# ConectoresSalida.net
KiCad netlist of a schematic drawn in Altium Designer
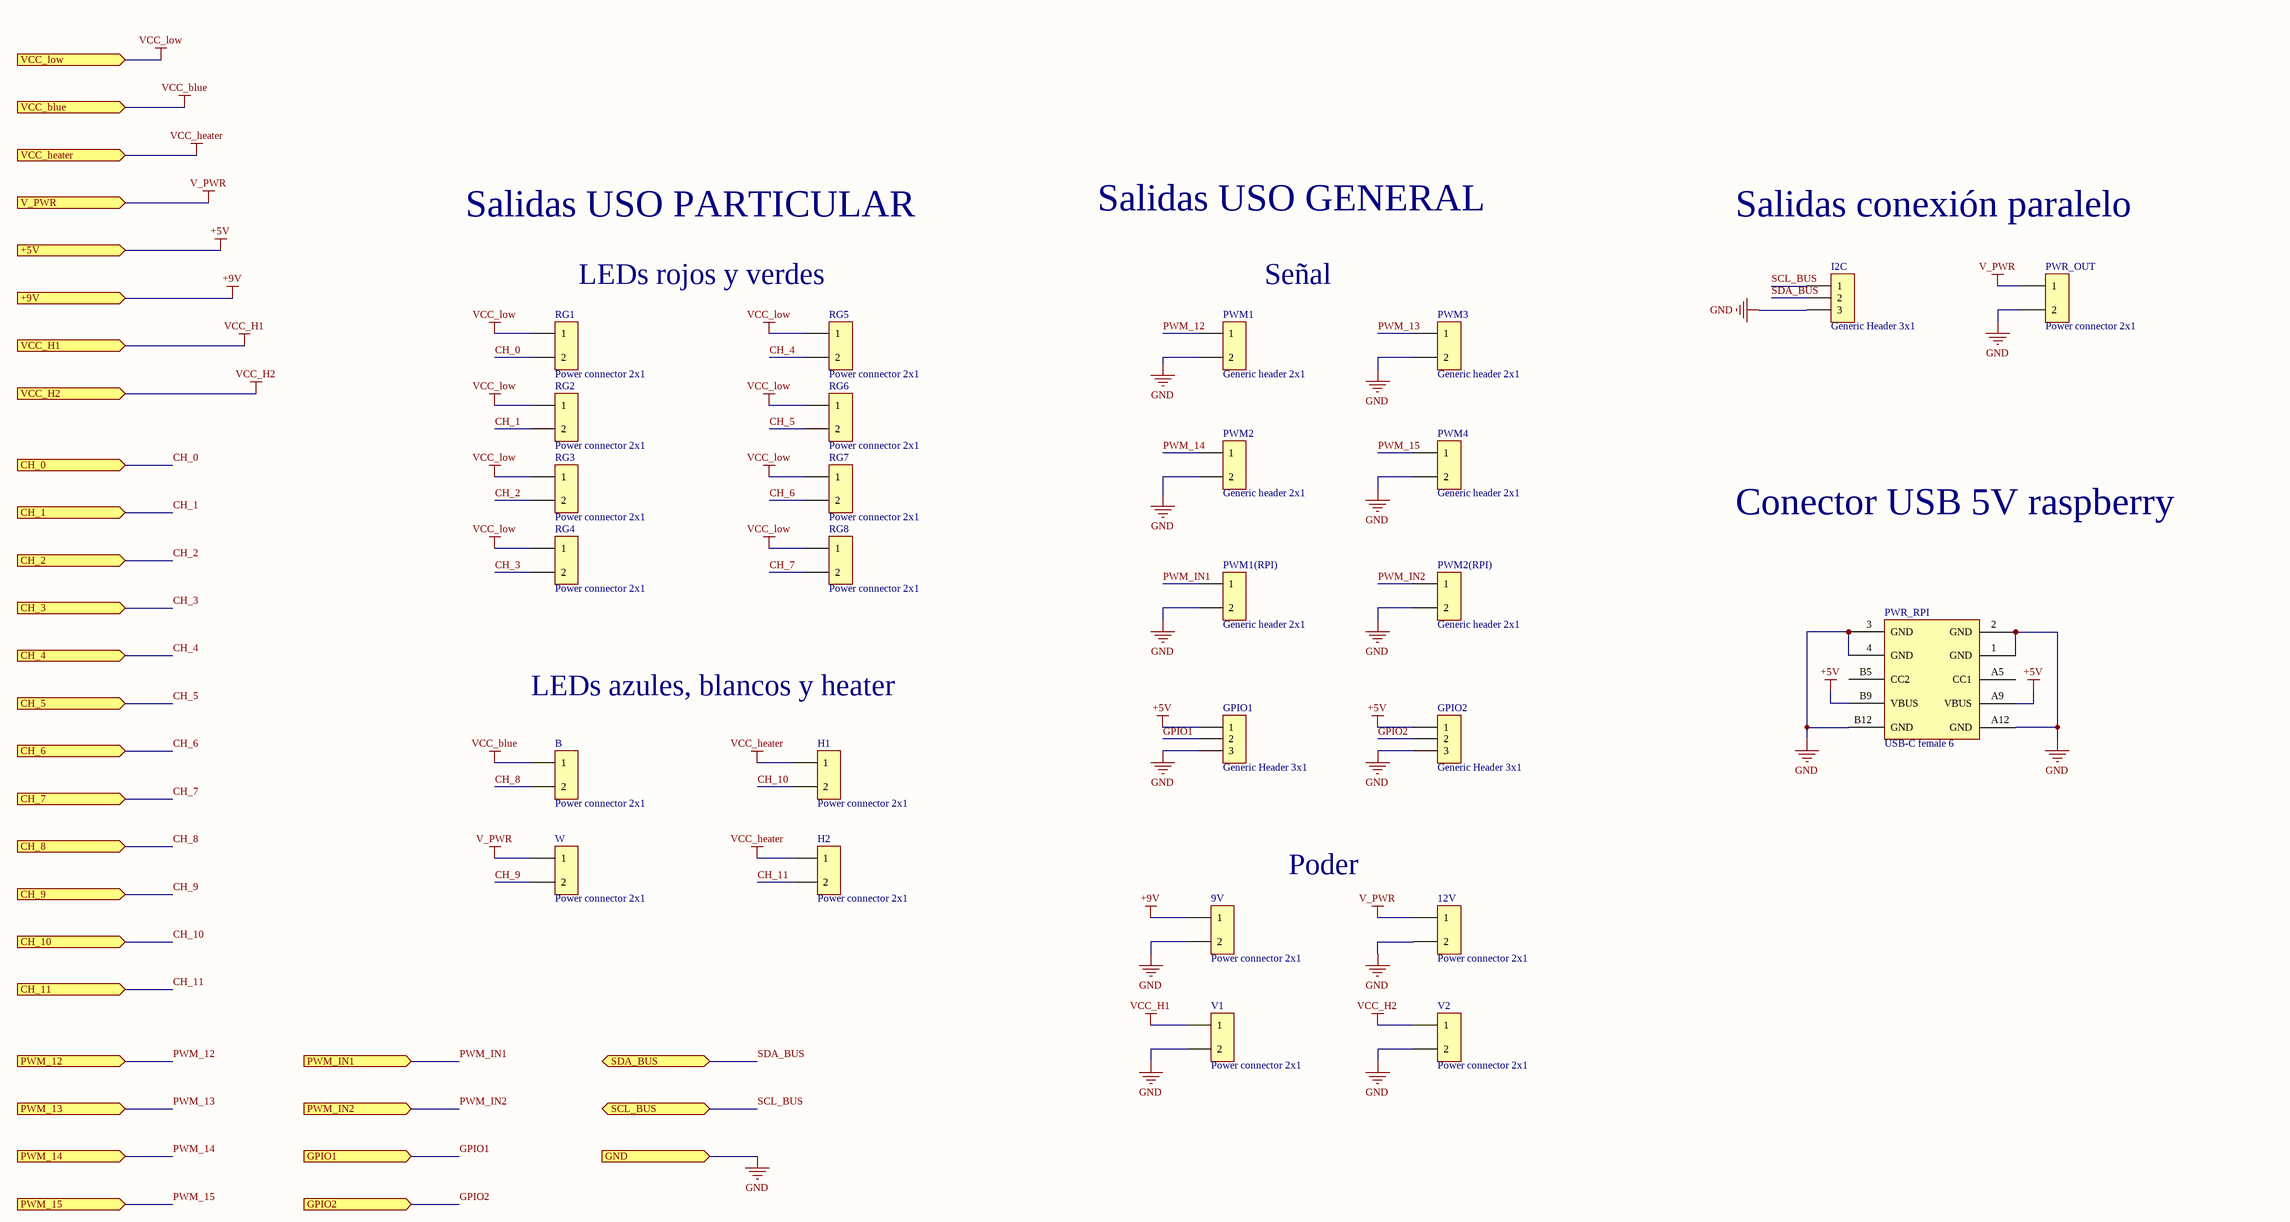
[diagram p0: ConectoresSalida.SchDoc]

(export (version "E")
  (design (tool "Eeschema 10.0.6"))
  (components
    (comp (ref "9V")
      (value "Power connector 2x1")
      (footprint "CONN-TH_430450212")
      (description "Generic Header Power 2pos")
      (fields (field (name "MANUFACTURER") "MOLEX") (field (name "MANUFACTURER PART NUMBER") "430450212"))
      (libsource (lib "IoWLabsConnectors") (part "PC - 2X1"))
    )
    (comp (ref "12V")
      (value "Power connector 2x1")
      (footprint "CONN-TH_430450212")
      (description "Generic Header Power 2pos")
      (fields (field (name "MANUFACTURER") "MOLEX") (field (name "MANUFACTURER PART NUMBER") "430450212"))
      (libsource (lib "IoWLabsConnectors") (part "PC - 2X1"))
    )
    (comp (ref "B")
      (value "Power connector 2x1")
      (footprint "CONN-TH_430450212")
      (description "Generic Header Power 2pos")
      (fields (field (name "MANUFACTURER") "MOLEX") (field (name "MANUFACTURER PART NUMBER") "430450212"))
      (libsource (lib "IoWLabsConnectors") (part "PC - 2X1"))
    )
    (comp (ref "GPIO1")
      (value "Generic Header 3x1")
      (footprint "CONN-TH_A2547WV-3P")
      (description "Generic Header 3pos, 1 row, 2.54 pitch")
      (fields
        (field (name "MANUFACTURER") "CJT(Changjiang Connectors)")
        (field (name "MANUFACTURER PART NUMBER") "A2547WV-3P")
      )
      (libsource (lib "IoWLabsConnectors") (part "Header - 3x1"))
    )
    (comp (ref "GPIO2")
      (value "Generic Header 3x1")
      (footprint "CONN-TH_A2547WV-3P")
      (description "Generic Header 3pos, 1 row, 2.54 pitch")
      (fields
        (field (name "MANUFACTURER") "CJT(Changjiang Connectors)")
        (field (name "MANUFACTURER PART NUMBER") "A2547WV-3P")
      )
      (libsource (lib "IoWLabsConnectors") (part "Header - 3x1"))
    )
    (comp (ref "H1")
      (value "Power connector 2x1")
      (footprint "CONN-TH_430450212")
      (description "Generic Header Power 2pos")
      (fields (field (name "MANUFACTURER") "MOLEX") (field (name "MANUFACTURER PART NUMBER") "430450212"))
      (libsource (lib "IoWLabsConnectors") (part "PC - 2X1"))
    )
    (comp (ref "H2")
      (value "Power connector 2x1")
      (footprint "CONN-TH_430450212")
      (description "Generic Header Power 2pos")
      (fields (field (name "MANUFACTURER") "MOLEX") (field (name "MANUFACTURER PART NUMBER") "430450212"))
      (libsource (lib "IoWLabsConnectors") (part "PC - 2X1"))
    )
    (comp (ref "I2C")
      (value "Generic Header 3x1")
      (footprint "CONN-TH_A2547WV-3P")
      (description "Generic Header 3pos, 1 row, 2.54 pitch")
      (fields
        (field (name "MANUFACTURER") "CJT(Changjiang Connectors)")
        (field (name "MANUFACTURER PART NUMBER") "A2547WV-3P")
      )
      (libsource (lib "IoWLabsConnectors") (part "Header - 3x1"))
    )
    (comp (ref "PWM1")
      (value "Generic header 2x1")
      (footprint "CONN-TH_A2547WV-2P")
      (description "Generic Header 2pos, 1 row, 2.54 pitch")
      (fields
        (field (name "MANUFACTURER") "CJT(Changjiang Connectors)")
        (field (name "MANUFACTURER PART NUMBER") "A2547WV-2P")
      )
      (libsource (lib "IoWLabsConnectors") (part "Header - 2x1"))
    )
    (comp (ref "PWM1(RPI)")
      (value "Generic header 2x1")
      (footprint "CONN-TH_A2547WV-2P")
      (description "Generic Header 2pos, 1 row, 2.54 pitch")
      (fields
        (field (name "MANUFACTURER") "CJT(Changjiang Connectors)")
        (field (name "MANUFACTURER PART NUMBER") "A2547WV-2P")
      )
      (libsource (lib "IoWLabsConnectors") (part "Header - 2x1"))
    )
    (comp (ref "PWM2")
      (value "Generic header 2x1")
      (footprint "CONN-TH_A2547WV-2P")
      (description "Generic Header 2pos, 1 row, 2.54 pitch")
      (fields
        (field (name "MANUFACTURER") "CJT(Changjiang Connectors)")
        (field (name "MANUFACTURER PART NUMBER") "A2547WV-2P")
      )
      (libsource (lib "IoWLabsConnectors") (part "Header - 2x1"))
    )
    (comp (ref "PWM2(RPI)")
      (value "Generic header 2x1")
      (footprint "CONN-TH_A2547WV-2P")
      (description "Generic Header 2pos, 1 row, 2.54 pitch")
      (fields
        (field (name "MANUFACTURER") "CJT(Changjiang Connectors)")
        (field (name "MANUFACTURER PART NUMBER") "A2547WV-2P")
      )
      (libsource (lib "IoWLabsConnectors") (part "Header - 2x1"))
    )
    (comp (ref "PWM3")
      (value "Generic header 2x1")
      (footprint "CONN-TH_A2547WV-2P")
      (description "Generic Header 2pos, 1 row, 2.54 pitch")
      (fields
        (field (name "MANUFACTURER") "CJT(Changjiang Connectors)")
        (field (name "MANUFACTURER PART NUMBER") "A2547WV-2P")
      )
      (libsource (lib "IoWLabsConnectors") (part "Header - 2x1"))
    )
    (comp (ref "PWM4")
      (value "Generic header 2x1")
      (footprint "CONN-TH_A2547WV-2P")
      (description "Generic Header 2pos, 1 row, 2.54 pitch")
      (fields
        (field (name "MANUFACTURER") "CJT(Changjiang Connectors)")
        (field (name "MANUFACTURER PART NUMBER") "A2547WV-2P")
      )
      (libsource (lib "IoWLabsConnectors") (part "Header - 2x1"))
    )
    (comp (ref "PWR_OUT")
      (value "Power connector 2x1")
      (footprint "CONN-TH_430450212")
      (description "Generic Header Power 2pos")
      (fields (field (name "MANUFACTURER") "MOLEX") (field (name "MANUFACTURER PART NUMBER") "430450212"))
      (libsource (lib "IoWLabsConnectors") (part "PC - 2X1"))
    )
    (comp (ref "PWR_RPI")
      (value "USB-C female 6")
      (footprint "USB-C_SMD 6 contacts")
      (description "USB - Type C Female 6 USB Connectors RoHS")
      (fields
        (field (name "MANUFACTURER") "Korean Hroparts Elec")
        (field (name "MANUFACTURER PART NUMBER") "TYPE-C-31-M-17")
      )
      (libsource (lib "IoWLabsConnectors") (part "USB-C female 6"))
    )
    (comp (ref "RG1")
      (value "Power connector 2x1")
      (footprint "CONN-TH_430450212")
      (description "Generic Header Power 2pos")
      (fields (field (name "MANUFACTURER") "MOLEX") (field (name "MANUFACTURER PART NUMBER") "430450212"))
      (libsource (lib "IoWLabsConnectors") (part "PC - 2X1"))
    )
    (comp (ref "RG2")
      (value "Power connector 2x1")
      (footprint "CONN-TH_430450212")
      (description "Generic Header Power 2pos")
      (fields (field (name "MANUFACTURER") "MOLEX") (field (name "MANUFACTURER PART NUMBER") "430450212"))
      (libsource (lib "IoWLabsConnectors") (part "PC - 2X1"))
    )
    (comp (ref "RG3")
      (value "Power connector 2x1")
      (footprint "CONN-TH_430450212")
      (description "Generic Header Power 2pos")
      (fields (field (name "MANUFACTURER") "MOLEX") (field (name "MANUFACTURER PART NUMBER") "430450212"))
      (libsource (lib "IoWLabsConnectors") (part "PC - 2X1"))
    )
    (comp (ref "RG4")
      (value "Power connector 2x1")
      (footprint "CONN-TH_430450212")
      (description "Generic Header Power 2pos")
      (fields (field (name "MANUFACTURER") "MOLEX") (field (name "MANUFACTURER PART NUMBER") "430450212"))
      (libsource (lib "IoWLabsConnectors") (part "PC - 2X1"))
    )
    (comp (ref "RG5")
      (value "Power connector 2x1")
      (footprint "CONN-TH_430450212")
      (description "Generic Header Power 2pos")
      (fields (field (name "MANUFACTURER") "MOLEX") (field (name "MANUFACTURER PART NUMBER") "430450212"))
      (libsource (lib "IoWLabsConnectors") (part "PC - 2X1"))
    )
    (comp (ref "RG6")
      (value "Power connector 2x1")
      (footprint "CONN-TH_430450212")
      (description "Generic Header Power 2pos")
      (fields (field (name "MANUFACTURER") "MOLEX") (field (name "MANUFACTURER PART NUMBER") "430450212"))
      (libsource (lib "IoWLabsConnectors") (part "PC - 2X1"))
    )
    (comp (ref "RG7")
      (value "Power connector 2x1")
      (footprint "CONN-TH_430450212")
      (description "Generic Header Power 2pos")
      (fields (field (name "MANUFACTURER") "MOLEX") (field (name "MANUFACTURER PART NUMBER") "430450212"))
      (libsource (lib "IoWLabsConnectors") (part "PC - 2X1"))
    )
    (comp (ref "RG8")
      (value "Power connector 2x1")
      (footprint "CONN-TH_430450212")
      (description "Generic Header Power 2pos")
      (fields (field (name "MANUFACTURER") "MOLEX") (field (name "MANUFACTURER PART NUMBER") "430450212"))
      (libsource (lib "IoWLabsConnectors") (part "PC - 2X1"))
    )
    (comp (ref "V1")
      (value "Power connector 2x1")
      (footprint "CONN-TH_430450212")
      (description "Generic Header Power 2pos")
      (fields (field (name "MANUFACTURER") "MOLEX") (field (name "MANUFACTURER PART NUMBER") "430450212"))
      (libsource (lib "IoWLabsConnectors") (part "PC - 2X1"))
    )
    (comp (ref "V2")
      (value "Power connector 2x1")
      (footprint "CONN-TH_430450212")
      (description "Generic Header Power 2pos")
      (fields (field (name "MANUFACTURER") "MOLEX") (field (name "MANUFACTURER PART NUMBER") "430450212"))
      (libsource (lib "IoWLabsConnectors") (part "PC - 2X1"))
    )
    (comp (ref "W")
      (value "Power connector 2x1")
      (footprint "CONN-TH_430450212")
      (description "Generic Header Power 2pos")
      (fields (field (name "MANUFACTURER") "MOLEX") (field (name "MANUFACTURER PART NUMBER") "430450212"))
      (libsource (lib "IoWLabsConnectors") (part "PC - 2X1"))
    )
  )
  (nets
    (net (code "1") (name "+5V") (class "Default")
      (node (ref "GPIO1") (pin "1") (pinfunction "1_1") (pintype "passive"))
      (node (ref "GPIO2") (pin "1") (pinfunction "1_1") (pintype "passive"))
      (node (ref "PWR_RPI") (pin "A9") (pinfunction "VBUS_A9") (pintype "passive"))
      (node (ref "PWR_RPI") (pin "B9") (pinfunction "VBUS_B9") (pintype "passive"))
    )
    (net (code "2") (name "+9V") (class "Default")
      (node (ref "9V") (pin "1") (pinfunction "1_1") (pintype "passive"))
    )
    (net (code "3") (name "/CH_0") (class "Default")
      (node (ref "RG1") (pin "2") (pinfunction "2_2") (pintype "passive"))
    )
    (net (code "4") (name "/CH_1") (class "Default")
      (node (ref "RG2") (pin "2") (pinfunction "2_2") (pintype "passive"))
    )
    (net (code "5") (name "/CH_2") (class "Default")
      (node (ref "RG3") (pin "2") (pinfunction "2_2") (pintype "passive"))
    )
    (net (code "6") (name "/CH_3") (class "Default")
      (node (ref "RG4") (pin "2") (pinfunction "2_2") (pintype "passive"))
    )
    (net (code "7") (name "/CH_4") (class "Default")
      (node (ref "RG5") (pin "2") (pinfunction "2_2") (pintype "passive"))
    )
    (net (code "8") (name "/CH_5") (class "Default")
      (node (ref "RG6") (pin "2") (pinfunction "2_2") (pintype "passive"))
    )
    (net (code "9") (name "/CH_6") (class "Default")
      (node (ref "RG7") (pin "2") (pinfunction "2_2") (pintype "passive"))
    )
    (net (code "10") (name "/CH_7") (class "Default")
      (node (ref "RG8") (pin "2") (pinfunction "2_2") (pintype "passive"))
    )
    (net (code "11") (name "/CH_8") (class "Default")
      (node (ref "B") (pin "2") (pinfunction "2_2") (pintype "passive"))
    )
    (net (code "12") (name "/CH_9") (class "Default")
      (node (ref "W") (pin "2") (pinfunction "2_2") (pintype "passive"))
    )
    (net (code "13") (name "/CH_10") (class "Default")
      (node (ref "H1") (pin "2") (pinfunction "2_2") (pintype "passive"))
    )
    (net (code "14") (name "/CH_11") (class "Default")
      (node (ref "H2") (pin "2") (pinfunction "2_2") (pintype "passive"))
    )
    (net (code "15") (name "/GPIO1") (class "Default")
      (node (ref "GPIO1") (pin "2") (pinfunction "2_2") (pintype "passive"))
    )
    (net (code "16") (name "/GPIO2") (class "Default")
      (node (ref "GPIO2") (pin "2") (pinfunction "2_2") (pintype "passive"))
    )
    (net (code "17") (name "/PWM_12") (class "Default")
      (node (ref "PWM1") (pin "1") (pinfunction "1_1") (pintype "passive"))
    )
    (net (code "18") (name "/PWM_13") (class "Default")
      (node (ref "PWM3") (pin "1") (pinfunction "1_1") (pintype "passive"))
    )
    (net (code "19") (name "/PWM_14") (class "Default")
      (node (ref "PWM2") (pin "1") (pinfunction "1_1") (pintype "passive"))
    )
    (net (code "20") (name "/PWM_15") (class "Default")
      (node (ref "PWM4") (pin "1") (pinfunction "1_1") (pintype "passive"))
    )
    (net (code "21") (name "/PWM_IN1") (class "Default")
      (node (ref "PWM1(RPI)") (pin "1") (pinfunction "1_1") (pintype "passive"))
    )
    (net (code "22") (name "/PWM_IN2") (class "Default")
      (node (ref "PWM2(RPI)") (pin "1") (pinfunction "1_1") (pintype "passive"))
    )
    (net (code "23") (name "/SCL_BUS") (class "Default")
      (node (ref "I2C") (pin "1") (pinfunction "1_1") (pintype "passive"))
    )
    (net (code "24") (name "/SDA_BUS") (class "Default")
      (node (ref "I2C") (pin "2") (pinfunction "2_2") (pintype "passive"))
    )
    (net (code "25") (name "GND") (class "Default")
      (node (ref "12V") (pin "2") (pinfunction "2_2") (pintype "passive"))
      (node (ref "9V") (pin "2") (pinfunction "2_2") (pintype "passive"))
      (node (ref "GPIO1") (pin "3") (pinfunction "3_3") (pintype "passive"))
      (node (ref "GPIO2") (pin "3") (pinfunction "3_3") (pintype "passive"))
      (node (ref "I2C") (pin "3") (pinfunction "3_3") (pintype "passive"))
      (node (ref "PWM1") (pin "2") (pinfunction "2_2") (pintype "passive"))
      (node (ref "PWM1(RPI)") (pin "2") (pinfunction "2_2") (pintype "passive"))
      (node (ref "PWM2") (pin "2") (pinfunction "2_2") (pintype "passive"))
      (node (ref "PWM2(RPI)") (pin "2") (pinfunction "2_2") (pintype "passive"))
      (node (ref "PWM3") (pin "2") (pinfunction "2_2") (pintype "passive"))
      (node (ref "PWM4") (pin "2") (pinfunction "2_2") (pintype "passive"))
      (node (ref "PWR_OUT") (pin "2") (pinfunction "2_2") (pintype "passive"))
      (node (ref "PWR_RPI") (pin "1") (pinfunction "GND_1") (pintype "passive"))
      (node (ref "PWR_RPI") (pin "2") (pinfunction "GND_2") (pintype "passive"))
      (node (ref "PWR_RPI") (pin "3") (pinfunction "GND_3") (pintype "passive"))
      (node (ref "PWR_RPI") (pin "4") (pinfunction "GND_4") (pintype "passive"))
      (node (ref "PWR_RPI") (pin "A12") (pinfunction "GND_A12") (pintype "passive"))
      (node (ref "PWR_RPI") (pin "B12") (pinfunction "GND_B12") (pintype "passive"))
      (node (ref "V1") (pin "2") (pinfunction "2_2") (pintype "passive"))
      (node (ref "V2") (pin "2") (pinfunction "2_2") (pintype "passive"))
    )
    (net (code "26") (name "VCC_H1") (class "Default")
      (node (ref "V1") (pin "1") (pinfunction "1_1") (pintype "passive"))
    )
    (net (code "27") (name "VCC_H2") (class "Default")
      (node (ref "V2") (pin "1") (pinfunction "1_1") (pintype "passive"))
    )
    (net (code "28") (name "VCC_blue") (class "Default")
      (node (ref "B") (pin "1") (pinfunction "1_1") (pintype "passive"))
    )
    (net (code "29") (name "VCC_heater") (class "Default")
      (node (ref "H1") (pin "1") (pinfunction "1_1") (pintype "passive"))
      (node (ref "H2") (pin "1") (pinfunction "1_1") (pintype "passive"))
    )
    (net (code "30") (name "VCC_low") (class "Default")
      (node (ref "RG1") (pin "1") (pinfunction "1_1") (pintype "passive"))
      (node (ref "RG2") (pin "1") (pinfunction "1_1") (pintype "passive"))
      (node (ref "RG3") (pin "1") (pinfunction "1_1") (pintype "passive"))
      (node (ref "RG4") (pin "1") (pinfunction "1_1") (pintype "passive"))
      (node (ref "RG5") (pin "1") (pinfunction "1_1") (pintype "passive"))
      (node (ref "RG6") (pin "1") (pinfunction "1_1") (pintype "passive"))
      (node (ref "RG7") (pin "1") (pinfunction "1_1") (pintype "passive"))
      (node (ref "RG8") (pin "1") (pinfunction "1_1") (pintype "passive"))
    )
    (net (code "31") (name "V_PWR") (class "Default")
      (node (ref "12V") (pin "1") (pinfunction "1_1") (pintype "passive"))
      (node (ref "PWR_OUT") (pin "1") (pinfunction "1_1") (pintype "passive"))
      (node (ref "W") (pin "1") (pinfunction "1_1") (pintype "passive"))
    )
    (net (code "32") (name "unconnected-(PWR_RPI-CC1-PadA5)") (class "Default")
      (node (ref "PWR_RPI") (pin "A5") (pinfunction "CC1_A5") (pintype "passive"))
    )
    (net (code "33") (name "unconnected-(PWR_RPI-CC2-PadB5)") (class "Default")
      (node (ref "PWR_RPI") (pin "B5") (pinfunction "CC2_B5") (pintype "passive"))
    )
  )
)
